# MaxOr.net
KiCad netlist of a schematic drawn in EAGLE
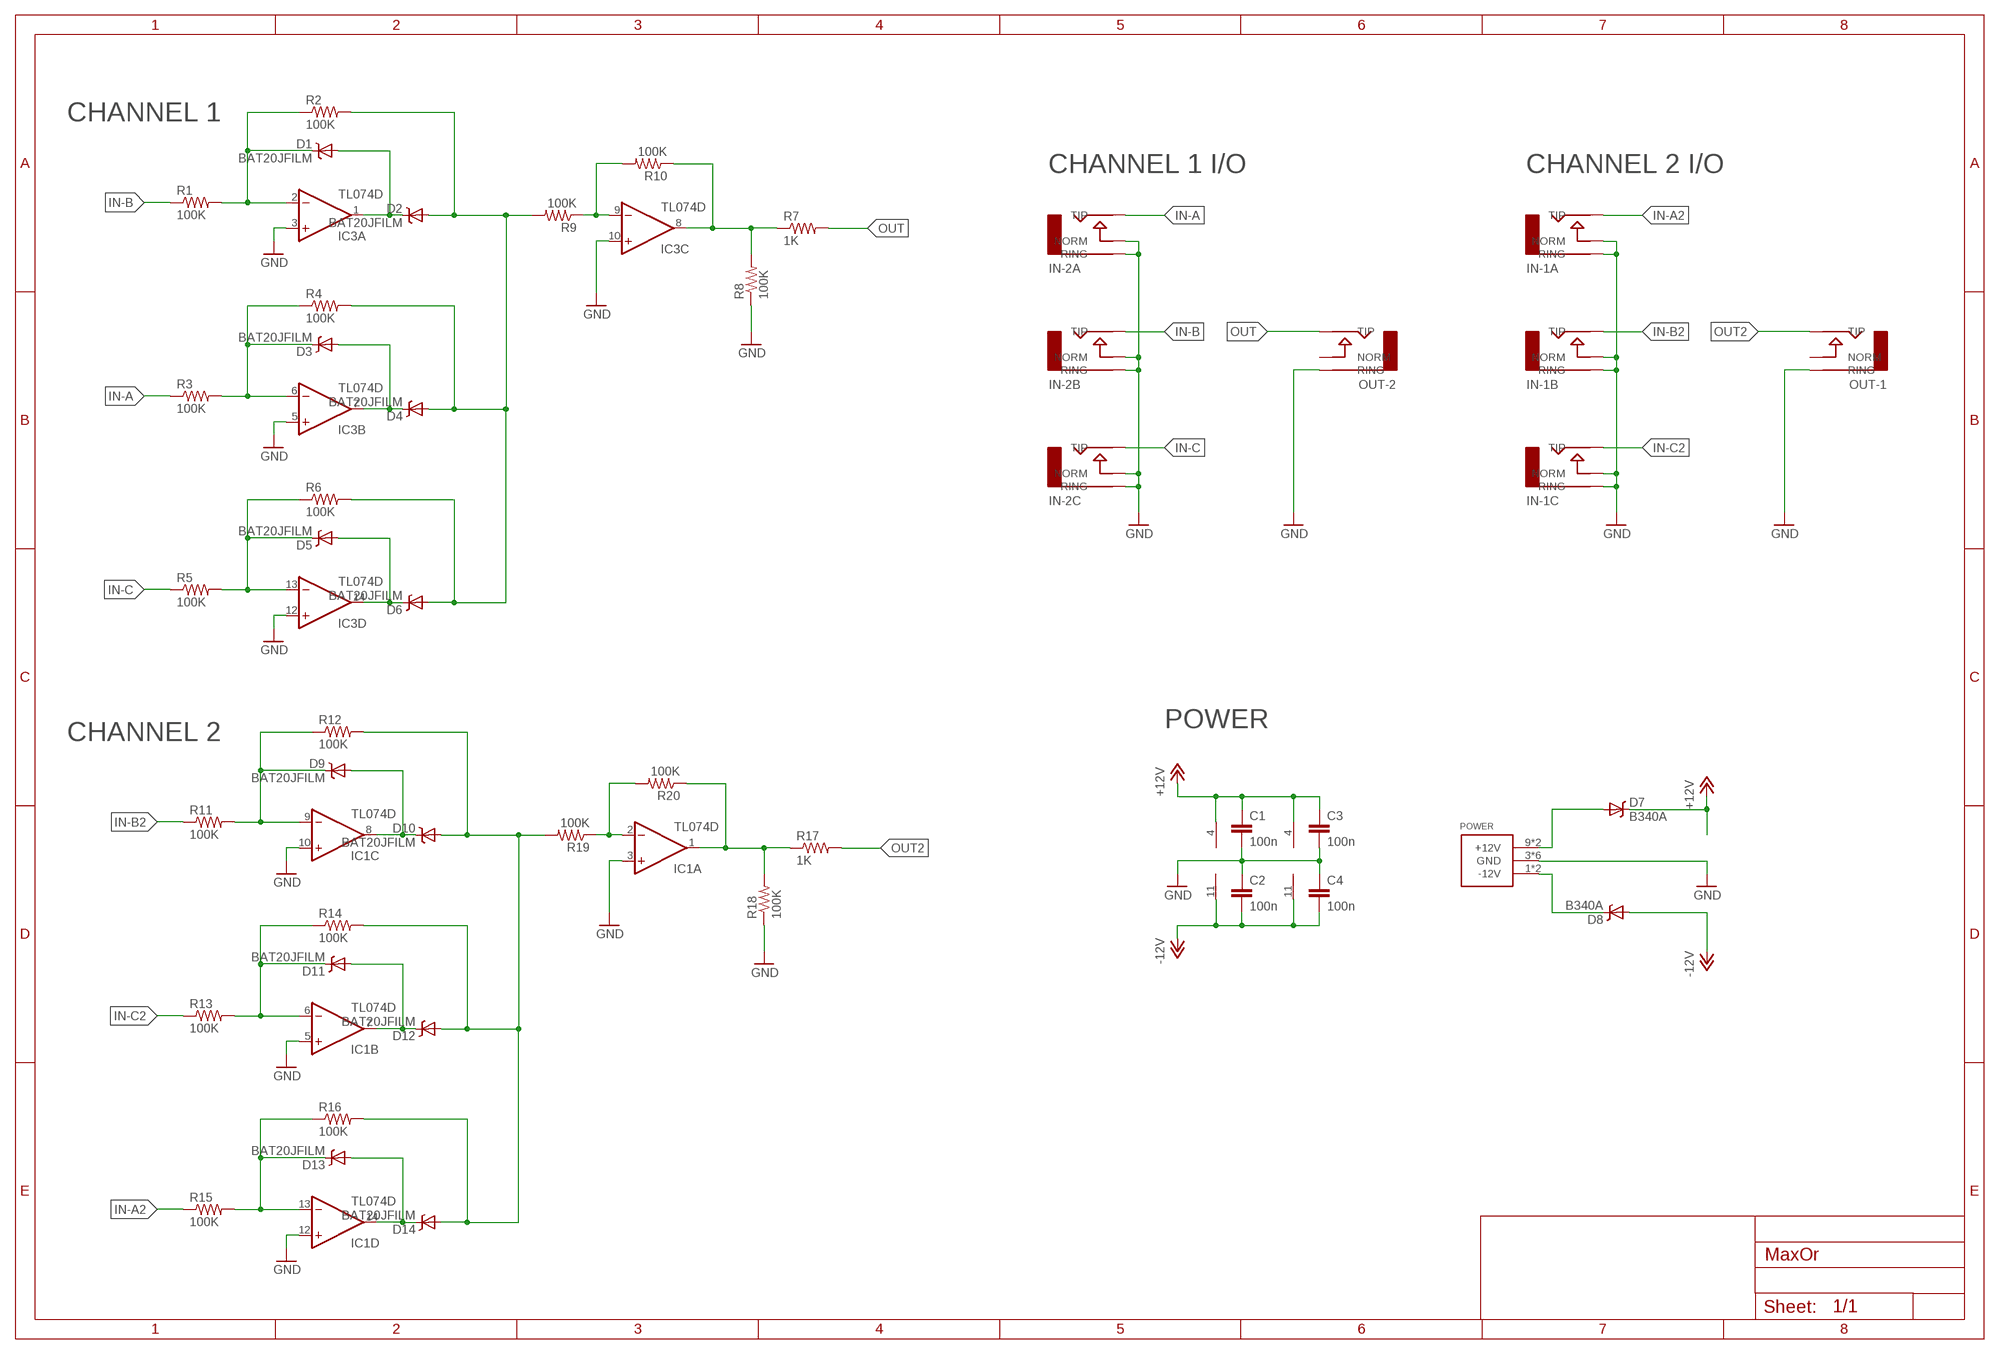
[diagram p0: schematic, sheet 1]

(export (version "E")
  (design (tool "Eeschema 10.0.6"))
  (components
    (comp (ref "C1")
      (value "100n")
      (footprint "eagle-import:0805")
      (libsource (lib "eagle-import") (part "CAP0805"))
    )
    (comp (ref "C2")
      (value "100n")
      (footprint "eagle-import:0805")
      (libsource (lib "eagle-import") (part "CAP0805"))
    )
    (comp (ref "C3")
      (value "100n")
      (footprint "eagle-import:0805")
      (libsource (lib "eagle-import") (part "CAP0805"))
    )
    (comp (ref "C4")
      (value "100n")
      (footprint "eagle-import:0805")
      (libsource (lib "eagle-import") (part "CAP0805"))
    )
    (comp (ref "D1")
      (value "BAT20JFILM")
      (footprint "eagle-import:SOD-323")
      (libsource (lib "eagle-import") (part "BAT20JFILM"))
    )
    (comp (ref "D2")
      (value "BAT20JFILM")
      (footprint "eagle-import:SOD-323")
      (libsource (lib "eagle-import") (part "BAT20JFILM"))
    )
    (comp (ref "D3")
      (value "BAT20JFILM")
      (footprint "eagle-import:SOD-323")
      (libsource (lib "eagle-import") (part "BAT20JFILM"))
    )
    (comp (ref "D4")
      (value "BAT20JFILM")
      (footprint "eagle-import:SOD-323")
      (libsource (lib "eagle-import") (part "BAT20JFILM"))
    )
    (comp (ref "D5")
      (value "BAT20JFILM")
      (footprint "eagle-import:SOD-323")
      (libsource (lib "eagle-import") (part "BAT20JFILM"))
    )
    (comp (ref "D6")
      (value "BAT20JFILM")
      (footprint "eagle-import:SOD-323")
      (libsource (lib "eagle-import") (part "BAT20JFILM"))
    )
    (comp (ref "D7")
      (value "B340A")
      (footprint "eagle-import:SMA-DIODE")
      (libsource (lib "eagle-import") (part "DIODE-SCHOTTKY-B340A"))
    )
    (comp (ref "D8")
      (value "B340A")
      (footprint "eagle-import:SMA-DIODE")
      (libsource (lib "eagle-import") (part "DIODE-SCHOTTKY-B340A"))
    )
    (comp (ref "D9")
      (value "BAT20JFILM")
      (footprint "eagle-import:SOD-323")
      (libsource (lib "eagle-import") (part "BAT20JFILM"))
    )
    (comp (ref "D10")
      (value "BAT20JFILM")
      (footprint "eagle-import:SOD-323")
      (libsource (lib "eagle-import") (part "BAT20JFILM"))
    )
    (comp (ref "D11")
      (value "BAT20JFILM")
      (footprint "eagle-import:SOD-323")
      (libsource (lib "eagle-import") (part "BAT20JFILM"))
    )
    (comp (ref "D12")
      (value "BAT20JFILM")
      (footprint "eagle-import:SOD-323")
      (libsource (lib "eagle-import") (part "BAT20JFILM"))
    )
    (comp (ref "D13")
      (value "BAT20JFILM")
      (footprint "eagle-import:SOD-323")
      (libsource (lib "eagle-import") (part "BAT20JFILM"))
    )
    (comp (ref "D14")
      (value "BAT20JFILM")
      (footprint "eagle-import:SOD-323")
      (libsource (lib "eagle-import") (part "BAT20JFILM"))
    )
    (comp (ref "IC1")
      (value "TL074D")
      (footprint "eagle-import:SO14")
      (libsource (lib "eagle-import") (part "TL074D"))
    )
    (comp (ref "IC3")
      (value "TL074D")
      (footprint "eagle-import:SO14")
      (libsource (lib "eagle-import") (part "TL074D"))
    )
    (comp (ref "IN-1A")
      (value "AUDIO-JACK")
      (footprint "eagle-import:ERTHENVAR-JACK-HORIZONTAL")
      (libsource (lib "eagle-import") (part "AUDIO-JACK"))
    )
    (comp (ref "IN-1B")
      (value "AUDIO-JACK")
      (footprint "eagle-import:ERTHENVAR-JACK-HORIZONTAL")
      (libsource (lib "eagle-import") (part "AUDIO-JACK"))
    )
    (comp (ref "IN-1C")
      (value "AUDIO-JACK")
      (footprint "eagle-import:ERTHENVAR-JACK-HORIZONTAL")
      (libsource (lib "eagle-import") (part "AUDIO-JACK"))
    )
    (comp (ref "IN-2A")
      (value "AUDIO-JACK")
      (footprint "eagle-import:ERTHENVAR-JACK-HORIZONTAL")
      (libsource (lib "eagle-import") (part "AUDIO-JACK"))
    )
    (comp (ref "IN-2B")
      (value "AUDIO-JACK")
      (footprint "eagle-import:ERTHENVAR-JACK-HORIZONTAL")
      (libsource (lib "eagle-import") (part "AUDIO-JACK"))
    )
    (comp (ref "IN-2C")
      (value "AUDIO-JACK")
      (footprint "eagle-import:ERTHENVAR-JACK-HORIZONTAL")
      (libsource (lib "eagle-import") (part "AUDIO-JACK"))
    )
    (comp (ref "OUT-1")
      (value "AUDIO-JACK")
      (footprint "eagle-import:ERTHENVAR-JACK-HORIZONTAL")
      (libsource (lib "eagle-import") (part "AUDIO-JACK"))
    )
    (comp (ref "OUT-2")
      (value "AUDIO-JACK")
      (footprint "eagle-import:ERTHENVAR-JACK-HORIZONTAL")
      (libsource (lib "eagle-import") (part "AUDIO-JACK"))
    )
    (comp (ref "POWER")
      (value "POWER_SIMPLE10")
      (footprint "eagle-import:POWER_10")
      (libsource (lib "eagle-import") (part "POWER_SIMPLE10"))
    )
    (comp (ref "R1")
      (value "100K")
      (footprint "eagle-import:0805")
      (libsource (lib "eagle-import") (part "RESISTOR0805-RES"))
    )
    (comp (ref "R2")
      (value "100K")
      (footprint "eagle-import:0805")
      (libsource (lib "eagle-import") (part "RESISTOR0805-RES"))
    )
    (comp (ref "R3")
      (value "100K")
      (footprint "eagle-import:0805")
      (libsource (lib "eagle-import") (part "RESISTOR0805-RES"))
    )
    (comp (ref "R4")
      (value "100K")
      (footprint "eagle-import:0805")
      (libsource (lib "eagle-import") (part "RESISTOR0805-RES"))
    )
    (comp (ref "R5")
      (value "100K")
      (footprint "eagle-import:0805")
      (libsource (lib "eagle-import") (part "RESISTOR0805-RES"))
    )
    (comp (ref "R6")
      (value "100K")
      (footprint "eagle-import:0805")
      (libsource (lib "eagle-import") (part "RESISTOR0805-RES"))
    )
    (comp (ref "R7")
      (value "1K")
      (footprint "eagle-import:0805")
      (libsource (lib "eagle-import") (part "RESISTOR0805-RES"))
    )
    (comp (ref "R8")
      (value "100K")
      (footprint "eagle-import:0805")
      (libsource (lib "eagle-import") (part "RESISTOR0805-RES"))
    )
    (comp (ref "R9")
      (value "100K")
      (footprint "eagle-import:0805")
      (libsource (lib "eagle-import") (part "RESISTOR0805-RES"))
    )
    (comp (ref "R10")
      (value "100K")
      (footprint "eagle-import:0805")
      (libsource (lib "eagle-import") (part "RESISTOR0805-RES"))
    )
    (comp (ref "R11")
      (value "100K")
      (footprint "eagle-import:0805")
      (libsource (lib "eagle-import") (part "RESISTOR0805-RES"))
    )
    (comp (ref "R12")
      (value "100K")
      (footprint "eagle-import:0805")
      (libsource (lib "eagle-import") (part "RESISTOR0805-RES"))
    )
    (comp (ref "R13")
      (value "100K")
      (footprint "eagle-import:0805")
      (libsource (lib "eagle-import") (part "RESISTOR0805-RES"))
    )
    (comp (ref "R14")
      (value "100K")
      (footprint "eagle-import:0805")
      (libsource (lib "eagle-import") (part "RESISTOR0805-RES"))
    )
    (comp (ref "R15")
      (value "100K")
      (footprint "eagle-import:0805")
      (libsource (lib "eagle-import") (part "RESISTOR0805-RES"))
    )
    (comp (ref "R16")
      (value "100K")
      (footprint "eagle-import:0805")
      (libsource (lib "eagle-import") (part "RESISTOR0805-RES"))
    )
    (comp (ref "R17")
      (value "1K")
      (footprint "eagle-import:0805")
      (libsource (lib "eagle-import") (part "RESISTOR0805-RES"))
    )
    (comp (ref "R18")
      (value "100K")
      (footprint "eagle-import:0805")
      (libsource (lib "eagle-import") (part "RESISTOR0805-RES"))
    )
    (comp (ref "R19")
      (value "100K")
      (footprint "eagle-import:0805")
      (libsource (lib "eagle-import") (part "RESISTOR0805-RES"))
    )
    (comp (ref "R20")
      (value "100K")
      (footprint "eagle-import:0805")
      (libsource (lib "eagle-import") (part "RESISTOR0805-RES"))
    )
  )
  (nets
    (net (code "1") (name "+12V") (class "Default")
      (node (ref "C1") (pin "1") (pinfunction "1_1") (pintype "passive"))
      (node (ref "C3") (pin "1") (pinfunction "1_1") (pintype "passive"))
      (node (ref "D7") (pin "C") (pinfunction "C_C") (pintype "passive"))
      (node (ref "IC1") (pin "4") (pinfunction "V+_4") (pintype "power_in"))
      (node (ref "IC3") (pin "4") (pinfunction "V+_4") (pintype "power_in"))
    )
    (net (code "2") (name "-12V") (class "Default")
      (node (ref "C2") (pin "2") (pinfunction "2_2") (pintype "passive"))
      (node (ref "C4") (pin "2") (pinfunction "2_2") (pintype "passive"))
      (node (ref "D8") (pin "A") (pinfunction "A_A") (pintype "passive"))
      (node (ref "IC1") (pin "11") (pinfunction "V-_11") (pintype "power_in"))
      (node (ref "IC3") (pin "11") (pinfunction "V-_11") (pintype "power_in"))
    )
    (net (code "3") (name "GND") (class "Default")
      (node (ref "C1") (pin "2") (pinfunction "2_2") (pintype "passive"))
      (node (ref "C2") (pin "1") (pinfunction "1_1") (pintype "passive"))
      (node (ref "C3") (pin "2") (pinfunction "2_2") (pintype "passive"))
      (node (ref "C4") (pin "1") (pinfunction "1_1") (pintype "passive"))
      (node (ref "IC1") (pin "10") (pinfunction "+IN_10") (pintype "input"))
      (node (ref "IC1") (pin "12") (pinfunction "+IN_12") (pintype "input"))
      (node (ref "IC1") (pin "3") (pinfunction "+IN_3") (pintype "input"))
      (node (ref "IC1") (pin "5") (pinfunction "+IN_5") (pintype "input"))
      (node (ref "IC3") (pin "10") (pinfunction "+IN_10") (pintype "input"))
      (node (ref "IC3") (pin "12") (pinfunction "+IN_12") (pintype "input"))
      (node (ref "IC3") (pin "3") (pinfunction "+IN_3") (pintype "input"))
      (node (ref "IC3") (pin "5") (pinfunction "+IN_5") (pintype "input"))
      (node (ref "IN-1A") (pin "N") (pinfunction "NORM_N") (pintype "bidirectional"))
      (node (ref "IN-1A") (pin "R@2") (pinfunction "RING_R@2") (pintype "bidirectional"))
      (node (ref "IN-1B") (pin "N") (pinfunction "NORM_N") (pintype "bidirectional"))
      (node (ref "IN-1B") (pin "R@2") (pinfunction "RING_R@2") (pintype "bidirectional"))
      (node (ref "IN-1C") (pin "N") (pinfunction "NORM_N") (pintype "bidirectional"))
      (node (ref "IN-1C") (pin "R@2") (pinfunction "RING_R@2") (pintype "bidirectional"))
      (node (ref "IN-2A") (pin "N") (pinfunction "NORM_N") (pintype "bidirectional"))
      (node (ref "IN-2A") (pin "R@2") (pinfunction "RING_R@2") (pintype "bidirectional"))
      (node (ref "IN-2B") (pin "N") (pinfunction "NORM_N") (pintype "bidirectional"))
      (node (ref "IN-2B") (pin "R@2") (pinfunction "RING_R@2") (pintype "bidirectional"))
      (node (ref "IN-2C") (pin "N") (pinfunction "NORM_N") (pintype "bidirectional"))
      (node (ref "IN-2C") (pin "R@2") (pinfunction "RING_R@2") (pintype "bidirectional"))
      (node (ref "OUT-1") (pin "R@2") (pinfunction "RING_R@2") (pintype "bidirectional"))
      (node (ref "OUT-2") (pin "R@2") (pinfunction "RING_R@2") (pintype "bidirectional"))
      (node (ref "POWER") (pin "3") (pinfunction "GND_3") (pintype "bidirectional"))
      (node (ref "POWER") (pin "4") (pinfunction "GND_4") (pintype "bidirectional"))
      (node (ref "POWER") (pin "5") (pinfunction "GND_5") (pintype "bidirectional"))
      (node (ref "POWER") (pin "6") (pinfunction "GND_6") (pintype "bidirectional"))
      (node (ref "POWER") (pin "7") (pinfunction "GND_7") (pintype "bidirectional"))
      (node (ref "POWER") (pin "8") (pinfunction "GND_8") (pintype "bidirectional"))
      (node (ref "R18") (pin "1") (pinfunction "1_1") (pintype "passive"))
      (node (ref "R8") (pin "1") (pinfunction "1_1") (pintype "passive"))
    )
    (net (code "4") (name "IN-A") (class "Default")
      (node (ref "IN-2A") (pin "T") (pinfunction "TIP_T") (pintype "bidirectional"))
      (node (ref "R3") (pin "1") (pinfunction "1_1") (pintype "passive"))
    )
    (net (code "5") (name "IN-A2") (class "Default")
      (node (ref "IN-1A") (pin "T") (pinfunction "TIP_T") (pintype "bidirectional"))
      (node (ref "R15") (pin "1") (pinfunction "1_1") (pintype "passive"))
    )
    (net (code "6") (name "IN-B") (class "Default")
      (node (ref "IN-2B") (pin "T") (pinfunction "TIP_T") (pintype "bidirectional"))
      (node (ref "R1") (pin "1") (pinfunction "1_1") (pintype "passive"))
    )
    (net (code "7") (name "IN-B2") (class "Default")
      (node (ref "IN-1B") (pin "T") (pinfunction "TIP_T") (pintype "bidirectional"))
      (node (ref "R11") (pin "1") (pinfunction "1_1") (pintype "passive"))
    )
    (net (code "8") (name "IN-C") (class "Default")
      (node (ref "IN-2C") (pin "T") (pinfunction "TIP_T") (pintype "bidirectional"))
      (node (ref "R5") (pin "1") (pinfunction "1_1") (pintype "passive"))
    )
    (net (code "9") (name "IN-C2") (class "Default")
      (node (ref "IN-1C") (pin "T") (pinfunction "TIP_T") (pintype "bidirectional"))
      (node (ref "R13") (pin "1") (pinfunction "1_1") (pintype "passive"))
    )
    (net (code "10") (name "Net-(D2-PadA)") (class "Default")
      (node (ref "D2") (pin "A") (pinfunction "A_A") (pintype "passive"))
      (node (ref "D4") (pin "A") (pinfunction "A_A") (pintype "passive"))
      (node (ref "D6") (pin "A") (pinfunction "A_A") (pintype "passive"))
      (node (ref "R2") (pin "2") (pinfunction "2_2") (pintype "passive"))
      (node (ref "R4") (pin "2") (pinfunction "2_2") (pintype "passive"))
      (node (ref "R6") (pin "2") (pinfunction "2_2") (pintype "passive"))
      (node (ref "R9") (pin "2") (pinfunction "2_2") (pintype "passive"))
    )
    (net (code "11") (name "Net-(D7-PadA)") (class "Default")
      (node (ref "D7") (pin "A") (pinfunction "A_A") (pintype "passive"))
      (node (ref "POWER") (pin "10") (pinfunction "+12V_10") (pintype "bidirectional"))
      (node (ref "POWER") (pin "9") (pinfunction "+12V_9") (pintype "bidirectional"))
    )
    (net (code "12") (name "Net-(D8-PadC)") (class "Default")
      (node (ref "D8") (pin "C") (pinfunction "C_C") (pintype "passive"))
      (node (ref "POWER") (pin "1") (pinfunction "-12V_1") (pintype "bidirectional"))
      (node (ref "POWER") (pin "2") (pinfunction "-12V_2") (pintype "bidirectional"))
    )
    (net (code "13") (name "Net-(D10-PadA)") (class "Default")
      (node (ref "D10") (pin "A") (pinfunction "A_A") (pintype "passive"))
      (node (ref "D12") (pin "A") (pinfunction "A_A") (pintype "passive"))
      (node (ref "D14") (pin "A") (pinfunction "A_A") (pintype "passive"))
      (node (ref "R12") (pin "2") (pinfunction "2_2") (pintype "passive"))
      (node (ref "R14") (pin "2") (pinfunction "2_2") (pintype "passive"))
      (node (ref "R16") (pin "2") (pinfunction "2_2") (pintype "passive"))
      (node (ref "R19") (pin "2") (pinfunction "2_2") (pintype "passive"))
    )
    (net (code "14") (name "Net-(IC1A--IN)") (class "Default")
      (node (ref "IC1") (pin "2") (pinfunction "-IN_2") (pintype "input"))
      (node (ref "R19") (pin "1") (pinfunction "1_1") (pintype "passive"))
      (node (ref "R20") (pin "2") (pinfunction "2_2") (pintype "passive"))
    )
    (net (code "15") (name "Net-(IC1A-OUT)") (class "Default")
      (node (ref "IC1") (pin "1") (pinfunction "OUT_1") (pintype "output"))
      (node (ref "R17") (pin "1") (pinfunction "1_1") (pintype "passive"))
      (node (ref "R18") (pin "2") (pinfunction "2_2") (pintype "passive"))
      (node (ref "R20") (pin "1") (pinfunction "1_1") (pintype "passive"))
    )
    (net (code "16") (name "Net-(IC1B--IN)") (class "Default")
      (node (ref "D11") (pin "C") (pinfunction "C_C") (pintype "passive"))
      (node (ref "IC1") (pin "6") (pinfunction "-IN_6") (pintype "input"))
      (node (ref "R13") (pin "2") (pinfunction "2_2") (pintype "passive"))
      (node (ref "R14") (pin "1") (pinfunction "1_1") (pintype "passive"))
    )
    (net (code "17") (name "Net-(IC1B-OUT)") (class "Default")
      (node (ref "D11") (pin "A") (pinfunction "A_A") (pintype "passive"))
      (node (ref "D12") (pin "C") (pinfunction "C_C") (pintype "passive"))
      (node (ref "IC1") (pin "7") (pinfunction "OUT_7") (pintype "output"))
    )
    (net (code "18") (name "Net-(IC1C--IN)") (class "Default")
      (node (ref "D9") (pin "C") (pinfunction "C_C") (pintype "passive"))
      (node (ref "IC1") (pin "9") (pinfunction "-IN_9") (pintype "input"))
      (node (ref "R11") (pin "2") (pinfunction "2_2") (pintype "passive"))
      (node (ref "R12") (pin "1") (pinfunction "1_1") (pintype "passive"))
    )
    (net (code "19") (name "Net-(IC1C-OUT)") (class "Default")
      (node (ref "D10") (pin "C") (pinfunction "C_C") (pintype "passive"))
      (node (ref "D9") (pin "A") (pinfunction "A_A") (pintype "passive"))
      (node (ref "IC1") (pin "8") (pinfunction "OUT_8") (pintype "output"))
    )
    (net (code "20") (name "Net-(IC1D--IN)") (class "Default")
      (node (ref "D13") (pin "C") (pinfunction "C_C") (pintype "passive"))
      (node (ref "IC1") (pin "13") (pinfunction "-IN_13") (pintype "input"))
      (node (ref "R15") (pin "2") (pinfunction "2_2") (pintype "passive"))
      (node (ref "R16") (pin "1") (pinfunction "1_1") (pintype "passive"))
    )
    (net (code "21") (name "Net-(IC1D-OUT)") (class "Default")
      (node (ref "D13") (pin "A") (pinfunction "A_A") (pintype "passive"))
      (node (ref "D14") (pin "C") (pinfunction "C_C") (pintype "passive"))
      (node (ref "IC1") (pin "14") (pinfunction "OUT_14") (pintype "output"))
    )
    (net (code "22") (name "Net-(IC3A--IN)") (class "Default")
      (node (ref "D1") (pin "C") (pinfunction "C_C") (pintype "passive"))
      (node (ref "IC3") (pin "2") (pinfunction "-IN_2") (pintype "input"))
      (node (ref "R1") (pin "2") (pinfunction "2_2") (pintype "passive"))
      (node (ref "R2") (pin "1") (pinfunction "1_1") (pintype "passive"))
    )
    (net (code "23") (name "Net-(IC3A-OUT)") (class "Default")
      (node (ref "D1") (pin "A") (pinfunction "A_A") (pintype "passive"))
      (node (ref "D2") (pin "C") (pinfunction "C_C") (pintype "passive"))
      (node (ref "IC3") (pin "1") (pinfunction "OUT_1") (pintype "output"))
    )
    (net (code "24") (name "Net-(IC3B--IN)") (class "Default")
      (node (ref "D3") (pin "C") (pinfunction "C_C") (pintype "passive"))
      (node (ref "IC3") (pin "6") (pinfunction "-IN_6") (pintype "input"))
      (node (ref "R3") (pin "2") (pinfunction "2_2") (pintype "passive"))
      (node (ref "R4") (pin "1") (pinfunction "1_1") (pintype "passive"))
    )
    (net (code "25") (name "Net-(IC3B-OUT)") (class "Default")
      (node (ref "D3") (pin "A") (pinfunction "A_A") (pintype "passive"))
      (node (ref "D4") (pin "C") (pinfunction "C_C") (pintype "passive"))
      (node (ref "IC3") (pin "7") (pinfunction "OUT_7") (pintype "output"))
    )
    (net (code "26") (name "Net-(IC3C--IN)") (class "Default")
      (node (ref "IC3") (pin "9") (pinfunction "-IN_9") (pintype "input"))
      (node (ref "R10") (pin "2") (pinfunction "2_2") (pintype "passive"))
      (node (ref "R9") (pin "1") (pinfunction "1_1") (pintype "passive"))
    )
    (net (code "27") (name "Net-(IC3C-OUT)") (class "Default")
      (node (ref "IC3") (pin "8") (pinfunction "OUT_8") (pintype "output"))
      (node (ref "R10") (pin "1") (pinfunction "1_1") (pintype "passive"))
      (node (ref "R7") (pin "1") (pinfunction "1_1") (pintype "passive"))
      (node (ref "R8") (pin "2") (pinfunction "2_2") (pintype "passive"))
    )
    (net (code "28") (name "Net-(IC3D--IN)") (class "Default")
      (node (ref "D5") (pin "C") (pinfunction "C_C") (pintype "passive"))
      (node (ref "IC3") (pin "13") (pinfunction "-IN_13") (pintype "input"))
      (node (ref "R5") (pin "2") (pinfunction "2_2") (pintype "passive"))
      (node (ref "R6") (pin "1") (pinfunction "1_1") (pintype "passive"))
    )
    (net (code "29") (name "Net-(IC3D-OUT)") (class "Default")
      (node (ref "D5") (pin "A") (pinfunction "A_A") (pintype "passive"))
      (node (ref "D6") (pin "C") (pinfunction "C_C") (pintype "passive"))
      (node (ref "IC3") (pin "14") (pinfunction "OUT_14") (pintype "output"))
    )
    (net (code "30") (name "OUT") (class "Default")
      (node (ref "OUT-2") (pin "T") (pinfunction "TIP_T") (pintype "bidirectional"))
      (node (ref "R7") (pin "2") (pinfunction "2_2") (pintype "passive"))
    )
    (net (code "31") (name "OUT2") (class "Default")
      (node (ref "OUT-1") (pin "T") (pinfunction "TIP_T") (pintype "bidirectional"))
      (node (ref "R17") (pin "2") (pinfunction "2_2") (pintype "passive"))
    )
    (net (code "32") (name "unconnected-(OUT-1-NORM-PadN)") (class "Default")
      (node (ref "OUT-1") (pin "N") (pinfunction "NORM_N") (pintype "bidirectional"))
    )
    (net (code "33") (name "unconnected-(OUT-2-NORM-PadN)") (class "Default")
      (node (ref "OUT-2") (pin "N") (pinfunction "NORM_N") (pintype "bidirectional"))
    )
  )
)
